# Breathalyzer_Board.net
KiCad netlist of a schematic drawn in EAGLE
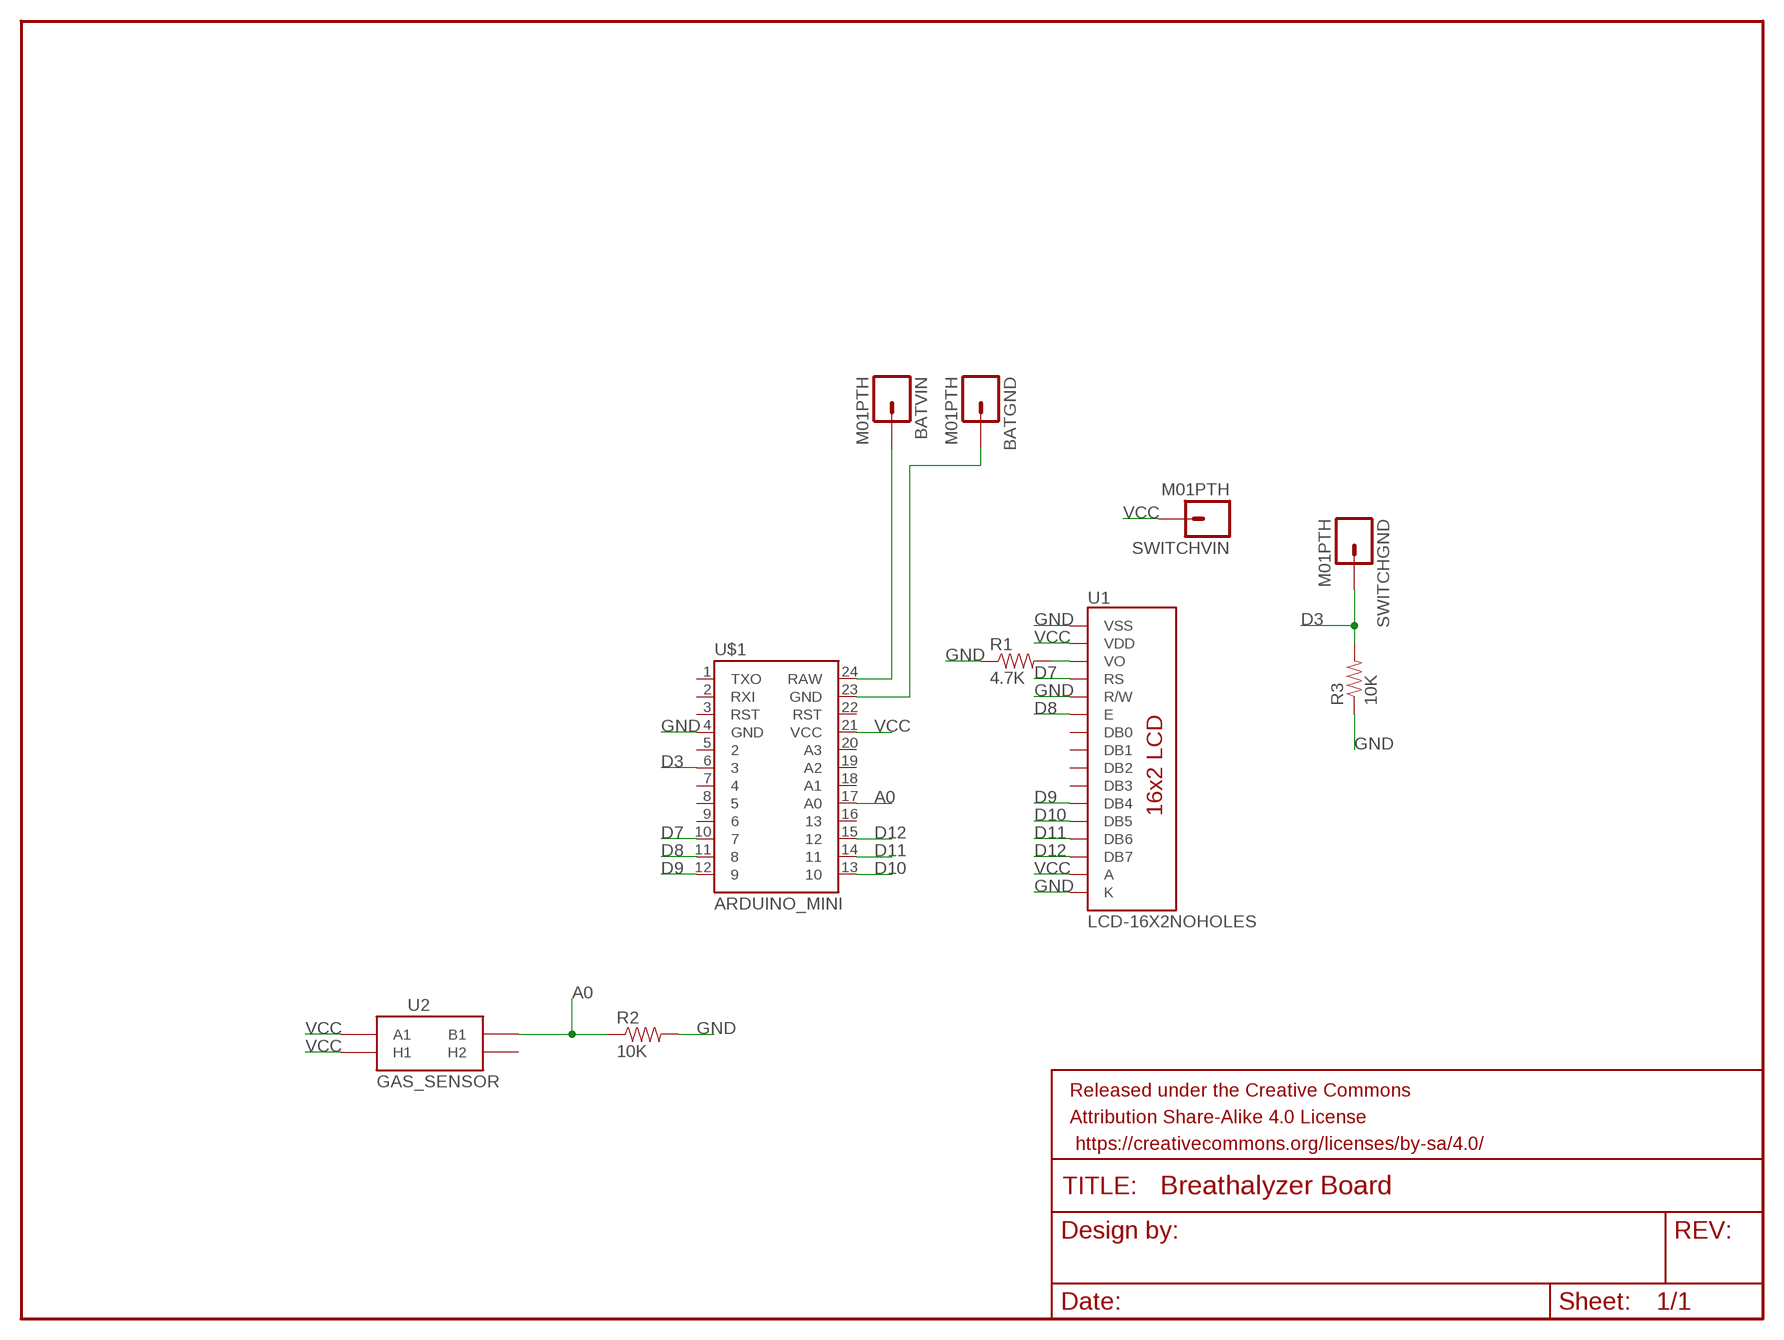
[diagram p0: schematic, sheet 1]

(export (version "E")
  (design (tool "Eeschema 10.0.6"))
  (components
    (comp (ref "BATGND")
      (value "M01PTH")
      (footprint "eagle-import:1X01")
      (libsource (lib "eagle-import") (part "M01PTH"))
    )
    (comp (ref "BATVIN")
      (value "M01PTH")
      (footprint "eagle-import:1X01")
      (libsource (lib "eagle-import") (part "M01PTH"))
    )
    (comp (ref "FRAME1")
      (value "FRAME-LETTER")
      (footprint "eagle-import:CREATIVE_COMMONS")
      (libsource (lib "eagle-import") (part "FRAME-LETTER"))
    )
    (comp (ref "R1")
      (value "4.7K")
      (footprint "eagle-import:AXIAL-0.3")
      (libsource (lib "eagle-import") (part "SparkFun-Resistors_RESISTORAXIAL-0.3"))
    )
    (comp (ref "R2")
      (value "10K")
      (footprint "eagle-import:AXIAL-0.3")
      (libsource (lib "eagle-import") (part "SparkFun-Resistors_RESISTORAXIAL-0.3"))
    )
    (comp (ref "R3")
      (value "10K")
      (footprint "eagle-import:AXIAL-0.3")
      (libsource (lib "eagle-import") (part "RESISTORAXIAL-0.3"))
    )
    (comp (ref "SWITCHGND")
      (value "M01PTH")
      (footprint "eagle-import:1X01")
      (libsource (lib "eagle-import") (part "M01PTH"))
    )
    (comp (ref "SWITCHVIN")
      (value "M01PTH")
      (footprint "eagle-import:1X01")
      (libsource (lib "eagle-import") (part "M01PTH"))
    )
    (comp (ref "U$1")
      (value "ARDUINO_MINI")
      (footprint "eagle-import:ARDUINO_MINI")
      (libsource (lib "eagle-import") (part "ARDUINO_MINI"))
    )
    (comp (ref "U1")
      (value "LCD-16X2NOHOLES")
      (footprint "eagle-import:LCD-16X2_NOHOLES")
      (libsource (lib "eagle-import") (part "LCD-16X2NOHOLES"))
    )
    (comp (ref "U2")
      (value "GAS_SENSOR")
      (footprint "eagle-import:MQ-3")
      (libsource (lib "eagle-import") (part "GAS_SENSOR"))
    )
  )
  (nets
    (net (code "1") (name "/A0") (class "Default")
      (node (ref "R2") (pin "P$1") (pinfunction "1_P$1") (pintype "passive"))
      (node (ref "U$1") (pin "17") (pinfunction "A0_17") (pintype "bidirectional"))
      (node (ref "U2") (pin "B1") (pinfunction "B1_B1") (pintype "bidirectional"))
    )
    (net (code "2") (name "/D3") (class "Default")
      (node (ref "R3") (pin "P$2") (pinfunction "2_P$2") (pintype "passive"))
      (node (ref "SWITCHGND") (pin "1") (pinfunction "1_1") (pintype "passive"))
      (node (ref "U$1") (pin "6") (pinfunction "3_6") (pintype "bidirectional"))
    )
    (net (code "3") (name "/D7") (class "Default")
      (node (ref "U$1") (pin "10") (pinfunction "7_10") (pintype "bidirectional"))
      (node (ref "U1") (pin "4") (pinfunction "RS_4") (pintype "input"))
    )
    (net (code "4") (name "/D8") (class "Default")
      (node (ref "U$1") (pin "11") (pinfunction "8_11") (pintype "bidirectional"))
      (node (ref "U1") (pin "6") (pinfunction "E_6") (pintype "input"))
    )
    (net (code "5") (name "/D9") (class "Default")
      (node (ref "U$1") (pin "12") (pinfunction "9_12") (pintype "bidirectional"))
      (node (ref "U1") (pin "11") (pinfunction "DB4_11") (pintype "bidirectional"))
    )
    (net (code "6") (name "/D10") (class "Default")
      (node (ref "U$1") (pin "13") (pinfunction "10_13") (pintype "bidirectional"))
      (node (ref "U1") (pin "12") (pinfunction "DB5_12") (pintype "bidirectional"))
    )
    (net (code "7") (name "/D11") (class "Default")
      (node (ref "U$1") (pin "14") (pinfunction "11_14") (pintype "bidirectional"))
      (node (ref "U1") (pin "13") (pinfunction "DB6_13") (pintype "bidirectional"))
    )
    (net (code "8") (name "/D12") (class "Default")
      (node (ref "U$1") (pin "15") (pinfunction "12_15") (pintype "bidirectional"))
      (node (ref "U1") (pin "14") (pinfunction "DB7_14") (pintype "bidirectional"))
    )
    (net (code "9") (name "/GND") (class "Default")
      (node (ref "R1") (pin "P$1") (pinfunction "1_P$1") (pintype "passive"))
      (node (ref "R2") (pin "P$2") (pinfunction "2_P$2") (pintype "passive"))
      (node (ref "R3") (pin "P$1") (pinfunction "1_P$1") (pintype "passive"))
      (node (ref "U$1") (pin "4") (pinfunction "GND_4") (pintype "bidirectional"))
      (node (ref "U1") (pin "1") (pinfunction "VSS_1") (pintype "power_in"))
      (node (ref "U1") (pin "16") (pinfunction "K_16") (pintype "power_in"))
      (node (ref "U1") (pin "5") (pinfunction "R/W_5") (pintype "input"))
    )
    (net (code "10") (name "/VCC") (class "Default")
      (node (ref "SWITCHVIN") (pin "1") (pinfunction "1_1") (pintype "passive"))
      (node (ref "U$1") (pin "21") (pinfunction "VCC_21") (pintype "bidirectional"))
      (node (ref "U1") (pin "15") (pinfunction "A_15") (pintype "power_in"))
      (node (ref "U1") (pin "2") (pinfunction "VDD_2") (pintype "power_in"))
      (node (ref "U2") (pin "A1") (pinfunction "A1_A1") (pintype "bidirectional"))
      (node (ref "U2") (pin "HA") (pinfunction "H1_HA") (pintype "bidirectional"))
    )
    (net (code "11") (name "Net-(BATGND-Pad1)") (class "Default")
      (node (ref "BATGND") (pin "1") (pinfunction "1_1") (pintype "passive"))
      (node (ref "U$1") (pin "23") (pinfunction "GND_23") (pintype "bidirectional"))
    )
    (net (code "12") (name "Net-(R1-2)") (class "Default")
      (node (ref "R1") (pin "P$2") (pinfunction "2_P$2") (pintype "passive"))
      (node (ref "U1") (pin "3") (pinfunction "VO_3") (pintype "bidirectional"))
    )
    (net (code "13") (name "Net-(U$1-RAW)") (class "Default")
      (node (ref "BATVIN") (pin "1") (pinfunction "1_1") (pintype "passive"))
      (node (ref "U$1") (pin "24") (pinfunction "RAW_24") (pintype "bidirectional"))
    )
    (net (code "14") (name "unconnected-(U$1-2-Pad5)") (class "Default")
      (node (ref "U$1") (pin "5") (pinfunction "2_5") (pintype "bidirectional"))
    )
    (net (code "15") (name "unconnected-(U$1-4-Pad7)") (class "Default")
      (node (ref "U$1") (pin "7") (pinfunction "4_7") (pintype "bidirectional"))
    )
    (net (code "16") (name "unconnected-(U$1-5-Pad8)") (class "Default")
      (node (ref "U$1") (pin "8") (pinfunction "5_8") (pintype "bidirectional"))
    )
    (net (code "17") (name "unconnected-(U$1-6-Pad9)") (class "Default")
      (node (ref "U$1") (pin "9") (pinfunction "6_9") (pintype "bidirectional"))
    )
    (net (code "18") (name "unconnected-(U$1-13-Pad16)") (class "Default")
      (node (ref "U$1") (pin "16") (pinfunction "13_16") (pintype "bidirectional"))
    )
    (net (code "19") (name "unconnected-(U$1-A1-Pad18)") (class "Default")
      (node (ref "U$1") (pin "18") (pinfunction "A1_18") (pintype "bidirectional"))
    )
    (net (code "20") (name "unconnected-(U$1-A2-Pad19)") (class "Default")
      (node (ref "U$1") (pin "19") (pinfunction "A2_19") (pintype "bidirectional"))
    )
    (net (code "21") (name "unconnected-(U$1-A3-Pad20)") (class "Default")
      (node (ref "U$1") (pin "20") (pinfunction "A3_20") (pintype "bidirectional"))
    )
    (net (code "22") (name "unconnected-(U$1-RST-Pad3)") (class "Default")
      (node (ref "U$1") (pin "3") (pinfunction "RST_3") (pintype "bidirectional"))
    )
    (net (code "23") (name "unconnected-(U$1-RST-Pad22)") (class "Default")
      (node (ref "U$1") (pin "22") (pinfunction "RST_22") (pintype "bidirectional"))
    )
    (net (code "24") (name "unconnected-(U$1-RXI-Pad2)") (class "Default")
      (node (ref "U$1") (pin "2") (pinfunction "RXI_2") (pintype "bidirectional"))
    )
    (net (code "25") (name "unconnected-(U$1-TXO-Pad1)") (class "Default")
      (node (ref "U$1") (pin "1") (pinfunction "TXO_1") (pintype "bidirectional"))
    )
    (net (code "26") (name "unconnected-(U1-DB0-Pad7)") (class "Default")
      (node (ref "U1") (pin "7") (pinfunction "DB0_7") (pintype "bidirectional"))
    )
    (net (code "27") (name "unconnected-(U1-DB1-Pad8)") (class "Default")
      (node (ref "U1") (pin "8") (pinfunction "DB1_8") (pintype "bidirectional"))
    )
    (net (code "28") (name "unconnected-(U1-DB2-Pad9)") (class "Default")
      (node (ref "U1") (pin "9") (pinfunction "DB2_9") (pintype "bidirectional"))
    )
    (net (code "29") (name "unconnected-(U1-DB3-Pad10)") (class "Default")
      (node (ref "U1") (pin "10") (pinfunction "DB3_10") (pintype "bidirectional"))
    )
    (net (code "30") (name "unconnected-(U2-H2-PadHB)") (class "Default")
      (node (ref "U2") (pin "HB") (pinfunction "H2_HB") (pintype "bidirectional"))
    )
  )
)
